# HDMI.net
KiCad netlist of a schematic drawn in Altium Designer
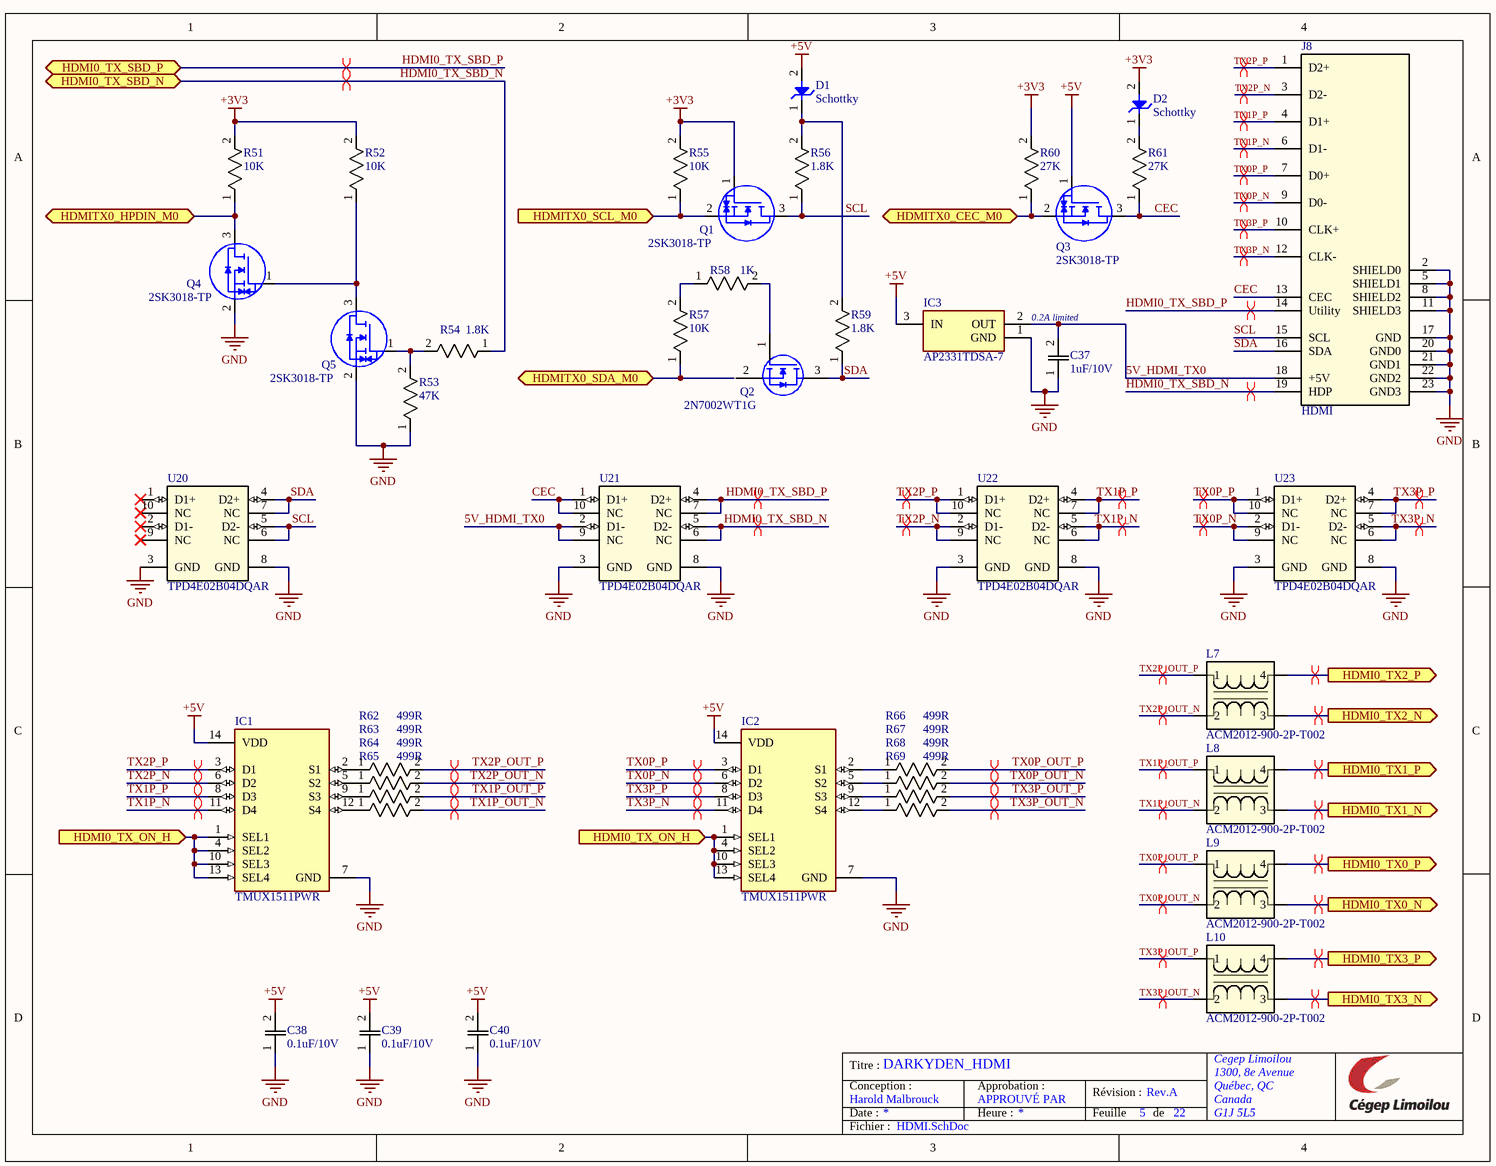
[diagram p0: HDMI.SchDoc]

(export (version "E")
  (design (tool "Eeschema 10.0.6"))
  (components
    (comp (ref "C37")
      (value "1uF/10V")
      (footprint "CAPC220145_100N_KEM")
      (description "Multilayer Ceramic Capacitors MLCC - SMD/SMT 10V 1uF X7R 0805 10%")
      (fields
        (field (name "MANUFACTURER") "KEMET")
        (field (name "MANUFACTURER PART NUMBER") "C0805C105K8RACTU")
      )
      (libsource (lib "C0805C105K8RACTU") (part "C0805C105K8RACTU"))
    )
    (comp (ref "C38")
      (value "0.1uF/10V")
      (footprint "CAPC220145_88N_KEM")
      (description "Cap Ceramic 0.1uF 10V X7R 5% Pad SMD 0805 125C T/R")
      (fields
        (field (name "MANUFACTURER") "KEMET")
        (field (name "MANUFACTURER PART NUMBER") "C0805C104J8RACTU")
      )
      (libsource (lib "C0805C104J8RACTU") (part "C0805C104J8RACTU"))
    )
    (comp (ref "C39")
      (value "0.1uF/10V")
      (footprint "CAPC220145_88N_KEM")
      (description "Cap Ceramic 0.1uF 10V X7R 5% Pad SMD 0805 125C T/R")
      (fields
        (field (name "MANUFACTURER") "KEMET")
        (field (name "MANUFACTURER PART NUMBER") "C0805C104J8RACTU")
      )
      (libsource (lib "C0805C104J8RACTU") (part "C0805C104J8RACTU"))
    )
    (comp (ref "C40")
      (value "0.1uF/10V")
      (footprint "CAPC220145_88N_KEM")
      (description "Cap Ceramic 0.1uF 10V X7R 5% Pad SMD 0805 125C T/R")
      (fields
        (field (name "MANUFACTURER") "KEMET")
        (field (name "MANUFACTURER PART NUMBER") "C0805C104J8RACTU")
      )
      (libsource (lib "C0805C104J8RACTU") (part "C0805C104J8RACTU"))
    )
    (comp (ref "D1")
      (value "Schottky")
      (footprint "SamacSys:SODFL1608X70N")
      (description "Diode -SOD523")
      (fields
        (field (name "MANUFACTURER_PART_NUMBER") "RB520S30T1G")
        (field (name "MOUSER PART NUMBER") "863-RB520S30T1G")
      )
      (libsource (lib "SamacSys") (part "Schottky"))
    )
    (comp (ref "D2")
      (value "Schottky")
      (footprint "SamacSys:SODFL1608X70N")
      (description "Diode -SOD523")
      (fields
        (field (name "MANUFACTURER_PART_NUMBER") "RB520S30T1G")
        (field (name "MOUSER PART NUMBER") "863-RB520S30T1G")
      )
      (libsource (lib "SamacSys") (part "Schottky"))
    )
    (comp (ref "IC1")
      (value "TMUX1511PWR")
      (footprint "SamacSys:SOP65P640X120-14N")
      (fields
        (field (name "MOUSER PART NUMBER") "595-TMUX1511PWR")
        (field (name "MANUFACTURER") "Texas Instruments")
      )
      (libsource (lib "SamacSys") (part "TMUX1511PWR"))
    )
    (comp (ref "IC2")
      (value "TMUX1511PWR")
      (footprint "SamacSys:SOP65P640X120-14N")
      (fields
        (field (name "MOUSER PART NUMBER") "595-TMUX1511PWR")
        (field (name "MANUFACTURER") "Texas Instruments")
      )
      (libsource (lib "SamacSys") (part "TMUX1511PWR"))
    )
    (comp (ref "IC3")
      (value "AP2331TDSA-7")
      (footprint "SamacSys:SOT96P240X110-3N")
      (description "USB Power Switch Single 5.2V 0.4A 3-Pin SOT-23 T/R")
      (fields (field (name "MOUSER PART NUMBER") "621-AP2331TDSA-7") (field (name "MANUFACTURER") "Diodes"))
      (libsource (lib "SamacSys") (part "AP2331TDSA-7"))
    )
    (comp (ref "J8")
      (value "HDMI")
      (footprint "CONN19_2001-1-2-21-00-BK_CNC")
      (description "2001-1-2-21-00-BK")
      (libsource (lib "HDMI") (part "HDMI"))
    )
    (comp (ref "L7")
      (value "ACM2012-900-2P-T002")
      (footprint "SamacSys:ACM20129002PT002")
      (description "Ferrite Beads Wirewound Common Mode Filter 90Ohm 100MHz 400mA 0805 T/R")
      (fields (field (name "MOUSER PART NUMBER") "810-ACM20129002PT002") (field (name "MANUFACTURER") "TDK"))
      (libsource (lib "SamacSys") (part "ACM2012-900-2P-T002"))
    )
    (comp (ref "L8")
      (value "ACM2012-900-2P-T002")
      (footprint "SamacSys:ACM20129002PT002")
      (description "Ferrite Beads Wirewound Common Mode Filter 90Ohm 100MHz 400mA 0805 T/R")
      (fields (field (name "MOUSER PART NUMBER") "810-ACM20129002PT002") (field (name "MANUFACTURER") "TDK"))
      (libsource (lib "SamacSys") (part "ACM2012-900-2P-T002"))
    )
    (comp (ref "L9")
      (value "ACM2012-900-2P-T002")
      (footprint "SamacSys:ACM20129002PT002")
      (description "Ferrite Beads Wirewound Common Mode Filter 90Ohm 100MHz 400mA 0805 T/R")
      (fields (field (name "MOUSER PART NUMBER") "810-ACM20129002PT002") (field (name "MANUFACTURER") "TDK"))
      (libsource (lib "SamacSys") (part "ACM2012-900-2P-T002"))
    )
    (comp (ref "L10")
      (value "ACM2012-900-2P-T002")
      (footprint "SamacSys:ACM20129002PT002")
      (description "Ferrite Beads Wirewound Common Mode Filter 90Ohm 100MHz 400mA 0805 T/R")
      (fields (field (name "MOUSER PART NUMBER") "810-ACM20129002PT002") (field (name "MANUFACTURER") "TDK"))
      (libsource (lib "SamacSys") (part "ACM2012-900-2P-T002"))
    )
    (comp (ref "Q1")
      (value "2SK3018-TP")
      (footprint "SamacSys:SOT65P228X120-3N")
      (description "N-Channel 30 V 100mA (Ta) 200mW (Ta) Surface Mount SOT-323")
      (fields (field (name "MOUSER PART NUMBER") "833-2SK3018-TP"))
      (libsource (lib "SamacSys") (part "2SK3018-TP"))
    )
    (comp (ref "Q2")
      (value "2N7002WT1G")
      (footprint "SOT-323-3_2P2X1P35_ONS")
      (description "No Description Available")
      (libsource (lib "2N7002WT1G") (part "2N7002WT1G"))
    )
    (comp (ref "Q3")
      (value "2SK3018-TP")
      (footprint "SamacSys:SOT65P228X120-3N")
      (description "N-Channel 30 V 100mA (Ta) 200mW (Ta) Surface Mount SOT-323")
      (fields (field (name "MOUSER PART NUMBER") "833-2SK3018-TP"))
      (libsource (lib "SamacSys") (part "2SK3018-TP"))
    )
    (comp (ref "Q4")
      (value "2SK3018-TP")
      (footprint "SamacSys:SOT65P228X120-3N")
      (description "N-Channel 30 V 100mA (Ta) 200mW (Ta) Surface Mount SOT-323")
      (fields (field (name "MOUSER PART NUMBER") "833-2SK3018-TP"))
      (libsource (lib "SamacSys") (part "2SK3018-TP"))
    )
    (comp (ref "Q5")
      (value "2SK3018-TP")
      (footprint "SamacSys:SOT65P228X120-3N")
      (description "N-Channel 30 V 100mA (Ta) 200mW (Ta) Surface Mount SOT-323")
      (fields (field (name "MOUSER PART NUMBER") "833-2SK3018-TP"))
      (libsource (lib "SamacSys") (part "2SK3018-TP"))
    )
    (comp (ref "R51")
      (value "10K")
      (footprint "SamacSys:ERJ3EKF1000V")
      (description "10K Ohm 5% Res Thick Film 0603  0.1W(1/10W) ±200ppm/C Pad SMD Automotive T/R")
      (fields
        (field (name "MANUFACTURER_PART_NUMBER") "ERJ-3GEYJ103V")
        (field (name "MOUSER PART NUMBER") "667-ERJ-3GEYJ103V")
      )
      (libsource (lib "SamacSys") (part "ERJ-3GEYJ103V"))
    )
    (comp (ref "R52")
      (value "10K")
      (footprint "SamacSys:ERJ3EKF1000V")
      (description "10K Ohm 5% Res Thick Film 0603  0.1W(1/10W) ±200ppm/C Pad SMD Automotive T/R")
      (fields
        (field (name "MANUFACTURER_PART_NUMBER") "ERJ-3GEYJ103V")
        (field (name "MOUSER PART NUMBER") "667-ERJ-3GEYJ103V")
      )
      (libsource (lib "SamacSys") (part "ERJ-3GEYJ103V"))
    )
    (comp (ref "R53")
      (value "47K")
      (footprint "RC0603N_PAN")
      (description "Resistor Thick Film 0603 47K Ohm 5% 1/10W 200ppm/C Molded SMD Punched Carrier T/R")
      (fields
        (field (name "MANUFACTURER") "Panasonic")
        (field (name "MANUFACTURER PART NUMBER") "ERJ-3GEYJ473V")
      )
      (libsource (lib "ERJ-3GEYJ473V") (part "ERJ-3GEYJ473V"))
    )
    (comp (ref "R54")
      (value "1.8K")
      (footprint "RC0603N_PAN")
      (description "SMD Chip Resistor, 1.8 kOhm, ± 5%, 100 mW, 0603 [1608 Metric], Thick Film, General Purpose")
      (fields
        (field (name "MANUFACTURER") "Panasonic")
        (field (name "MANUFACTURER PART NUMBER") "ERJ-3GEYJ182V")
      )
      (libsource (lib "ERJ-3GEYJ182V") (part "ERJ-3GEYJ182V"))
    )
    (comp (ref "R55")
      (value "10K")
      (footprint "SamacSys:ERJ3EKF1000V")
      (description "10K Ohm 5% Res Thick Film 0603  0.1W(1/10W) ±200ppm/C Pad SMD Automotive T/R")
      (fields
        (field (name "MANUFACTURER_PART_NUMBER") "ERJ-3GEYJ103V")
        (field (name "MOUSER PART NUMBER") "667-ERJ-3GEYJ103V")
      )
      (libsource (lib "SamacSys") (part "ERJ-3GEYJ103V"))
    )
    (comp (ref "R56")
      (value "1.8K")
      (footprint "RC0603N_PAN")
      (description "SMD Chip Resistor, 1.8 kOhm, ± 5%, 100 mW, 0603 [1608 Metric], Thick Film, General Purpose")
      (fields
        (field (name "MANUFACTURER") "Panasonic")
        (field (name "MANUFACTURER PART NUMBER") "ERJ-3GEYJ182V")
      )
      (libsource (lib "ERJ-3GEYJ182V") (part "ERJ-3GEYJ182V"))
    )
    (comp (ref "R57")
      (value "10K")
      (footprint "SamacSys:ERJ3EKF1000V")
      (description "10K Ohm 5% Res Thick Film 0603  0.1W(1/10W) ±200ppm/C Pad SMD Automotive T/R")
      (fields
        (field (name "MANUFACTURER_PART_NUMBER") "ERJ-3GEYJ103V")
        (field (name "MOUSER PART NUMBER") "667-ERJ-3GEYJ103V")
      )
      (libsource (lib "SamacSys") (part "ERJ-3GEYJ103V"))
    )
    (comp (ref "R58")
      (value "1K")
      (footprint "SamacSys:RESC1608X55N")
      (description "1K Ohm 1% 1/10W Res Thick Film 0603 ±100ppm/°C Molded SMD Punched Carrier T/R")
      (fields
        (field (name "MANUFACTURER_PART_NUMBER") "ERJ-3EKF1001V")
        (field (name "MOUSER PART NUMBER") "667-ERJ-3EKF1001V")
      )
      (libsource (lib "SamacSys") (part "ERJ-3EKF1001V"))
    )
    (comp (ref "R59")
      (value "1.8K")
      (footprint "RC0603N_PAN")
      (description "SMD Chip Resistor, 1.8 kOhm, ± 5%, 100 mW, 0603 [1608 Metric], Thick Film, General Purpose")
      (fields
        (field (name "MANUFACTURER") "Panasonic")
        (field (name "MANUFACTURER PART NUMBER") "ERJ-3GEYJ182V")
      )
      (libsource (lib "ERJ-3GEYJ182V") (part "ERJ-3GEYJ182V"))
    )
    (comp (ref "R60")
      (value "27K")
      (footprint "RC0603N_PAN")
      (description "Res Thick Film 0603 27K Ohm 1% 1/10W ±100ppm/°C Molded SMD Punched Carrier T/R")
      (fields
        (field (name "MANUFACTURER") "Panasonic")
        (field (name "MANUFACTURER PART NUMBER") "ERJ-3EKF2702V")
      )
      (libsource (lib "ERJ-3EKF2702V") (part "ERJ-3EKF2702V"))
    )
    (comp (ref "R61")
      (value "27K")
      (footprint "RC0603N_PAN")
      (description "Res Thick Film 0603 27K Ohm 1% 1/10W ±100ppm/°C Molded SMD Punched Carrier T/R")
      (fields
        (field (name "MANUFACTURER") "Panasonic")
        (field (name "MANUFACTURER PART NUMBER") "ERJ-3EKF2702V")
      )
      (libsource (lib "ERJ-3EKF2702V") (part "ERJ-3EKF2702V"))
    )
    (comp (ref "R62")
      (value "499R")
      (footprint "RC0603N_PAN")
      (description "SMD Chip Resistor, 499 Ohm, ï¿½ 1%, 100 mW, 0603 [1608 Metric], Thick Film, Precision")
      (fields
        (field (name "MANUFACTURER") "Panasonic")
        (field (name "MANUFACTURER PART NUMBER") "ERJ-3EKF4990V")
      )
      (libsource (lib "ERJ-3EKF4990V") (part "ERJ-3EKF4990V"))
    )
    (comp (ref "R63")
      (value "499R")
      (footprint "RC0603N_PAN")
      (description "SMD Chip Resistor, 499 Ohm, ï¿½ 1%, 100 mW, 0603 [1608 Metric], Thick Film, Precision")
      (fields
        (field (name "MANUFACTURER") "Panasonic")
        (field (name "MANUFACTURER PART NUMBER") "ERJ-3EKF4990V")
      )
      (libsource (lib "ERJ-3EKF4990V") (part "ERJ-3EKF4990V"))
    )
    (comp (ref "R64")
      (value "499R")
      (footprint "RC0603N_PAN")
      (description "SMD Chip Resistor, 499 Ohm, ï¿½ 1%, 100 mW, 0603 [1608 Metric], Thick Film, Precision")
      (fields
        (field (name "MANUFACTURER") "Panasonic")
        (field (name "MANUFACTURER PART NUMBER") "ERJ-3EKF4990V")
      )
      (libsource (lib "ERJ-3EKF4990V") (part "ERJ-3EKF4990V"))
    )
    (comp (ref "R65")
      (value "499R")
      (footprint "RC0603N_PAN")
      (description "SMD Chip Resistor, 499 Ohm, ï¿½ 1%, 100 mW, 0603 [1608 Metric], Thick Film, Precision")
      (fields
        (field (name "MANUFACTURER") "Panasonic")
        (field (name "MANUFACTURER PART NUMBER") "ERJ-3EKF4990V")
      )
      (libsource (lib "ERJ-3EKF4990V") (part "ERJ-3EKF4990V"))
    )
    (comp (ref "R66")
      (value "499R")
      (footprint "RC0603N_PAN")
      (description "SMD Chip Resistor, 499 Ohm, ï¿½ 1%, 100 mW, 0603 [1608 Metric], Thick Film, Precision")
      (fields
        (field (name "MANUFACTURER") "Panasonic")
        (field (name "MANUFACTURER PART NUMBER") "ERJ-3EKF4990V")
      )
      (libsource (lib "ERJ-3EKF4990V") (part "ERJ-3EKF4990V"))
    )
    (comp (ref "R67")
      (value "499R")
      (footprint "RC0603N_PAN")
      (description "SMD Chip Resistor, 499 Ohm, ï¿½ 1%, 100 mW, 0603 [1608 Metric], Thick Film, Precision")
      (fields
        (field (name "MANUFACTURER") "Panasonic")
        (field (name "MANUFACTURER PART NUMBER") "ERJ-3EKF4990V")
      )
      (libsource (lib "ERJ-3EKF4990V") (part "ERJ-3EKF4990V"))
    )
    (comp (ref "R68")
      (value "499R")
      (footprint "RC0603N_PAN")
      (description "SMD Chip Resistor, 499 Ohm, ï¿½ 1%, 100 mW, 0603 [1608 Metric], Thick Film, Precision")
      (fields
        (field (name "MANUFACTURER") "Panasonic")
        (field (name "MANUFACTURER PART NUMBER") "ERJ-3EKF4990V")
      )
      (libsource (lib "ERJ-3EKF4990V") (part "ERJ-3EKF4990V"))
    )
    (comp (ref "R69")
      (value "499R")
      (footprint "RC0603N_PAN")
      (description "SMD Chip Resistor, 499 Ohm, ï¿½ 1%, 100 mW, 0603 [1608 Metric], Thick Film, Precision")
      (fields
        (field (name "MANUFACTURER") "Panasonic")
        (field (name "MANUFACTURER PART NUMBER") "ERJ-3EKF4990V")
      )
      (libsource (lib "ERJ-3EKF4990V") (part "ERJ-3EKF4990V"))
    )
    (comp (ref "U20")
      (value "TPD4E02B04DQAR")
      (footprint "DQA0010A")
      (description "TVS DIODE 3.6V 8.8V 10USON / 4-Channel ESD Protection Diode for USB Type-C and HDMI 2.0")
      (fields (field (name "MANUFACTURER") "Texas Instruments"))
      (libsource (lib "TPD4E02B04DQAR") (part "TPD4E02B04DQAR"))
    )
    (comp (ref "U21")
      (value "TPD4E02B04DQAR")
      (footprint "DQA0010A")
      (description "TVS DIODE 3.6V 8.8V 10USON / 4-Channel ESD Protection Diode for USB Type-C and HDMI 2.0")
      (fields (field (name "MANUFACTURER") "Texas Instruments"))
      (libsource (lib "TPD4E02B04DQAR") (part "TPD4E02B04DQAR"))
    )
    (comp (ref "U22")
      (value "TPD4E02B04DQAR")
      (footprint "DQA0010A")
      (description "TVS DIODE 3.6V 8.8V 10USON / 4-Channel ESD Protection Diode for USB Type-C and HDMI 2.0")
      (fields (field (name "MANUFACTURER") "Texas Instruments"))
      (libsource (lib "TPD4E02B04DQAR") (part "TPD4E02B04DQAR"))
    )
    (comp (ref "U23")
      (value "TPD4E02B04DQAR")
      (footprint "DQA0010A")
      (description "TVS DIODE 3.6V 8.8V 10USON / 4-Channel ESD Protection Diode for USB Type-C and HDMI 2.0")
      (fields (field (name "MANUFACTURER") "Texas Instruments"))
      (libsource (lib "TPD4E02B04DQAR") (part "TPD4E02B04DQAR"))
    )
  )
  (nets
    (net (code "1") (name "+3V3") (class "Default")
      (node (ref "D2") (pin "2") (pinfunction "A_2") (pintype "passive"))
      (node (ref "Q1") (pin "1") (pinfunction "G_1") (pintype "passive"))
      (node (ref "R51") (pin "2") (pinfunction "2_2") (pintype "passive"))
      (node (ref "R52") (pin "2") (pinfunction "2_2") (pintype "passive"))
      (node (ref "R55") (pin "2") (pinfunction "2_2") (pintype "passive"))
      (node (ref "R60") (pin "2") (pinfunction "2_2") (pintype "passive"))
    )
    (net (code "2") (name "+5V") (class "Default")
      (node (ref "C38") (pin "2") (pinfunction "2_2") (pintype "passive"))
      (node (ref "C39") (pin "2") (pinfunction "2_2") (pintype "passive"))
      (node (ref "C40") (pin "2") (pinfunction "2_2") (pintype "passive"))
      (node (ref "D1") (pin "2") (pinfunction "A_2") (pintype "passive"))
      (node (ref "IC1") (pin "14") (pinfunction "VDD_14") (pintype "power_in"))
      (node (ref "IC2") (pin "14") (pinfunction "VDD_14") (pintype "power_in"))
      (node (ref "IC3") (pin "3") (pinfunction "IN_3") (pintype "passive"))
      (node (ref "Q3") (pin "1") (pinfunction "G_1") (pintype "passive"))
    )
    (net (code "3") (name "/5V_HDMI_TX0") (class "Default")
      (node (ref "C37") (pin "2") (pinfunction "2_2") (pintype "passive"))
      (node (ref "IC3") (pin "2") (pinfunction "OUT_2") (pintype "passive"))
      (node (ref "J8") (pin "18") (pinfunction "+5V_18") (pintype "passive"))
      (node (ref "U21") (pin "2") (pinfunction "D1-_2") (pintype "bidirectional"))
      (node (ref "U21") (pin "9") (pinfunction "NC_9") (pintype "passive"))
    )
    (net (code "4") (name "/CEC") (class "Default")
      (node (ref "J8") (pin "13") (pinfunction "CEC_13") (pintype "passive"))
      (node (ref "Q3") (pin "3") (pinfunction "D_3") (pintype "passive"))
      (node (ref "R61") (pin "1") (pinfunction "1_1") (pintype "passive"))
      (node (ref "U21") (pin "1") (pinfunction "D1+_1") (pintype "bidirectional"))
      (node (ref "U21") (pin "10") (pinfunction "NC_10") (pintype "passive"))
    )
    (net (code "5") (name "/HDMI0_TX0_N") (class "Default")
      (node (ref "L9") (pin "3") (pinfunction "3_3") (pintype "passive"))
    )
    (net (code "6") (name "/HDMI0_TX0_P") (class "Default")
      (node (ref "L9") (pin "4") (pinfunction "4_4") (pintype "passive"))
    )
    (net (code "7") (name "/HDMI0_TX1_N") (class "Default")
      (node (ref "L8") (pin "3") (pinfunction "3_3") (pintype "passive"))
    )
    (net (code "8") (name "/HDMI0_TX1_P") (class "Default")
      (node (ref "L8") (pin "4") (pinfunction "4_4") (pintype "passive"))
    )
    (net (code "9") (name "/HDMI0_TX2_N") (class "Default")
      (node (ref "L7") (pin "3") (pinfunction "3_3") (pintype "passive"))
    )
    (net (code "10") (name "/HDMI0_TX2_P") (class "Default")
      (node (ref "L7") (pin "4") (pinfunction "4_4") (pintype "passive"))
    )
    (net (code "11") (name "/HDMI0_TX3_N") (class "Default")
      (node (ref "L10") (pin "3") (pinfunction "3_3") (pintype "passive"))
    )
    (net (code "12") (name "/HDMI0_TX3_P") (class "Default")
      (node (ref "L10") (pin "4") (pinfunction "4_4") (pintype "passive"))
    )
    (net (code "13") (name "/HDMI0_TX_ON_H") (class "Default")
      (node (ref "IC1") (pin "1") (pinfunction "SEL1_1") (pintype "input"))
      (node (ref "IC1") (pin "10") (pinfunction "SEL3_10") (pintype "input"))
      (node (ref "IC1") (pin "13") (pinfunction "SEL4_13") (pintype "input"))
      (node (ref "IC1") (pin "4") (pinfunction "SEL2_4") (pintype "input"))
      (node (ref "IC2") (pin "1") (pinfunction "SEL1_1") (pintype "input"))
      (node (ref "IC2") (pin "10") (pinfunction "SEL3_10") (pintype "input"))
      (node (ref "IC2") (pin "13") (pinfunction "SEL4_13") (pintype "input"))
      (node (ref "IC2") (pin "4") (pinfunction "SEL2_4") (pintype "input"))
    )
    (net (code "14") (name "/HDMI0_TX_SBD_N") (class "Default")
      (node (ref "J8") (pin "19") (pinfunction "HDP_19") (pintype "passive"))
      (node (ref "R54") (pin "1") (pinfunction "1_1") (pintype "passive"))
      (node (ref "U21") (pin "5") (pinfunction "D2-_5") (pintype "bidirectional"))
      (node (ref "U21") (pin "6") (pinfunction "NC_6") (pintype "passive"))
    )
    (net (code "15") (name "/HDMI0_TX_SBD_P") (class "Default")
      (node (ref "J8") (pin "14") (pinfunction "Utility_14") (pintype "passive"))
      (node (ref "U21") (pin "4") (pinfunction "D2+_4") (pintype "bidirectional"))
      (node (ref "U21") (pin "7") (pinfunction "NC_7") (pintype "passive"))
    )
    (net (code "16") (name "/HDMITX0_CEC_M0") (class "Default")
      (node (ref "Q3") (pin "2") (pinfunction "S_2") (pintype "passive"))
      (node (ref "R60") (pin "1") (pinfunction "1_1") (pintype "passive"))
    )
    (net (code "17") (name "/HDMITX0_HPDIN_M0") (class "Default")
      (node (ref "Q4") (pin "3") (pinfunction "D_3") (pintype "passive"))
      (node (ref "R51") (pin "1") (pinfunction "1_1") (pintype "passive"))
    )
    (net (code "18") (name "/HDMITX0_SCL_M0") (class "Default")
      (node (ref "Q1") (pin "2") (pinfunction "S_2") (pintype "passive"))
      (node (ref "R55") (pin "1") (pinfunction "1_1") (pintype "passive"))
    )
    (net (code "19") (name "/HDMITX0_SDA_M0") (class "Default")
      (node (ref "R57") (pin "1") (pinfunction "1_1") (pintype "passive"))
    )
    (net (code "20") (name "/SCL") (class "Default")
      (node (ref "J8") (pin "15") (pinfunction "SCL_15") (pintype "passive"))
      (node (ref "Q1") (pin "3") (pinfunction "D_3") (pintype "passive"))
      (node (ref "R56") (pin "1") (pinfunction "1_1") (pintype "passive"))
      (node (ref "U20") (pin "5") (pinfunction "D2-_5") (pintype "bidirectional"))
      (node (ref "U20") (pin "6") (pinfunction "NC_6") (pintype "passive"))
    )
    (net (code "21") (name "/SDA") (class "Default")
      (node (ref "J8") (pin "16") (pinfunction "SDA_16") (pintype "passive"))
      (node (ref "Q2") (pin "3") (pinfunction "DRAIN_3") (pintype "passive"))
      (node (ref "R59") (pin "1") (pinfunction "1_1") (pintype "passive"))
      (node (ref "U20") (pin "4") (pinfunction "D2+_4") (pintype "bidirectional"))
      (node (ref "U20") (pin "7") (pinfunction "NC_7") (pintype "passive"))
    )
    (net (code "22") (name "/TX0P_N") (class "Default")
      (node (ref "IC2") (pin "6") (pinfunction "D2_6") (pintype "bidirectional"))
      (node (ref "J8") (pin "9") (pinfunction "D0-_9") (pintype "passive"))
      (node (ref "U23") (pin "2") (pinfunction "D1-_2") (pintype "bidirectional"))
      (node (ref "U23") (pin "9") (pinfunction "NC_9") (pintype "passive"))
    )
    (net (code "23") (name "/TX0P_OUT_N") (class "Default")
      (node (ref "L9") (pin "2") (pinfunction "2_2") (pintype "passive"))
      (node (ref "R67") (pin "2") (pinfunction "2_2") (pintype "passive"))
    )
    (net (code "24") (name "/TX0P_OUT_P") (class "Default")
      (node (ref "L9") (pin "1") (pinfunction "1_1") (pintype "passive"))
      (node (ref "R66") (pin "2") (pinfunction "2_2") (pintype "passive"))
    )
    (net (code "25") (name "/TX0P_P") (class "Default")
      (node (ref "IC2") (pin "3") (pinfunction "D1_3") (pintype "bidirectional"))
      (node (ref "J8") (pin "7") (pinfunction "D0+_7") (pintype "passive"))
      (node (ref "U23") (pin "1") (pinfunction "D1+_1") (pintype "bidirectional"))
      (node (ref "U23") (pin "10") (pinfunction "NC_10") (pintype "passive"))
    )
    (net (code "26") (name "/TX1P_N") (class "Default")
      (node (ref "IC1") (pin "11") (pinfunction "D4_11") (pintype "bidirectional"))
      (node (ref "J8") (pin "6") (pinfunction "D1-_6") (pintype "passive"))
      (node (ref "U22") (pin "5") (pinfunction "D2-_5") (pintype "bidirectional"))
      (node (ref "U22") (pin "6") (pinfunction "NC_6") (pintype "passive"))
    )
    (net (code "27") (name "/TX1P_OUT_N") (class "Default")
      (node (ref "L8") (pin "2") (pinfunction "2_2") (pintype "passive"))
      (node (ref "R65") (pin "2") (pinfunction "2_2") (pintype "passive"))
    )
    (net (code "28") (name "/TX1P_OUT_P") (class "Default")
      (node (ref "L8") (pin "1") (pinfunction "1_1") (pintype "passive"))
      (node (ref "R64") (pin "2") (pinfunction "2_2") (pintype "passive"))
    )
    (net (code "29") (name "/TX1P_P") (class "Default")
      (node (ref "IC1") (pin "8") (pinfunction "D3_8") (pintype "bidirectional"))
      (node (ref "J8") (pin "4") (pinfunction "D1+_4") (pintype "passive"))
      (node (ref "U22") (pin "4") (pinfunction "D2+_4") (pintype "bidirectional"))
      (node (ref "U22") (pin "7") (pinfunction "NC_7") (pintype "passive"))
    )
    (net (code "30") (name "/TX2P_N") (class "Default")
      (node (ref "IC1") (pin "6") (pinfunction "D2_6") (pintype "bidirectional"))
      (node (ref "J8") (pin "3") (pinfunction "D2-_3") (pintype "passive"))
      (node (ref "U22") (pin "2") (pinfunction "D1-_2") (pintype "bidirectional"))
      (node (ref "U22") (pin "9") (pinfunction "NC_9") (pintype "passive"))
    )
    (net (code "31") (name "/TX2P_OUT_N") (class "Default")
      (node (ref "L7") (pin "2") (pinfunction "2_2") (pintype "passive"))
      (node (ref "R63") (pin "2") (pinfunction "2_2") (pintype "passive"))
    )
    (net (code "32") (name "/TX2P_OUT_P") (class "Default")
      (node (ref "L7") (pin "1") (pinfunction "1_1") (pintype "passive"))
      (node (ref "R62") (pin "2") (pinfunction "2_2") (pintype "passive"))
    )
    (net (code "33") (name "/TX2P_P") (class "Default")
      (node (ref "IC1") (pin "3") (pinfunction "D1_3") (pintype "bidirectional"))
      (node (ref "J8") (pin "1") (pinfunction "D2+_1") (pintype "passive"))
      (node (ref "U22") (pin "1") (pinfunction "D1+_1") (pintype "bidirectional"))
      (node (ref "U22") (pin "10") (pinfunction "NC_10") (pintype "passive"))
    )
    (net (code "34") (name "/TX3P_N") (class "Default")
      (node (ref "IC2") (pin "11") (pinfunction "D4_11") (pintype "bidirectional"))
      (node (ref "J8") (pin "12") (pinfunction "CLK-_12") (pintype "passive"))
      (node (ref "U23") (pin "5") (pinfunction "D2-_5") (pintype "bidirectional"))
      (node (ref "U23") (pin "6") (pinfunction "NC_6") (pintype "passive"))
    )
    (net (code "35") (name "/TX3P_OUT_N") (class "Default")
      (node (ref "L10") (pin "2") (pinfunction "2_2") (pintype "passive"))
      (node (ref "R69") (pin "2") (pinfunction "2_2") (pintype "passive"))
    )
    (net (code "36") (name "/TX3P_OUT_P") (class "Default")
      (node (ref "L10") (pin "1") (pinfunction "1_1") (pintype "passive"))
      (node (ref "R68") (pin "2") (pinfunction "2_2") (pintype "passive"))
    )
    (net (code "37") (name "/TX3P_P") (class "Default")
      (node (ref "IC2") (pin "8") (pinfunction "D3_8") (pintype "bidirectional"))
      (node (ref "J8") (pin "10") (pinfunction "CLK+_10") (pintype "passive"))
      (node (ref "U23") (pin "4") (pinfunction "D2+_4") (pintype "bidirectional"))
      (node (ref "U23") (pin "7") (pinfunction "NC_7") (pintype "passive"))
    )
    (net (code "38") (name "GND") (class "Default")
      (node (ref "C37") (pin "1") (pinfunction "1_1") (pintype "passive"))
      (node (ref "C38") (pin "1") (pinfunction "1_1") (pintype "passive"))
      (node (ref "C39") (pin "1") (pinfunction "1_1") (pintype "passive"))
      (node (ref "C40") (pin "1") (pinfunction "1_1") (pintype "passive"))
      (node (ref "IC1") (pin "7") (pinfunction "GND_7") (pintype "power_in"))
      (node (ref "IC2") (pin "7") (pinfunction "GND_7") (pintype "power_in"))
      (node (ref "IC3") (pin "1") (pinfunction "GND_1") (pintype "passive"))
      (node (ref "J8") (pin "11") (pinfunction "SHIELD3_11") (pintype "passive"))
      (node (ref "J8") (pin "17") (pinfunction "GND_17") (pintype "passive"))
      (node (ref "J8") (pin "2") (pinfunction "SHIELD0_2") (pintype "passive"))
      (node (ref "J8") (pin "20") (pinfunction "GND0_20") (pintype "passive"))
      (node (ref "J8") (pin "21") (pinfunction "GND1_21") (pintype "passive"))
      (node (ref "J8") (pin "22") (pinfunction "GND2_22") (pintype "passive"))
      (node (ref "J8") (pin "23") (pinfunction "GND3_23") (pintype "passive"))
      (node (ref "J8") (pin "5") (pinfunction "SHIELD1_5") (pintype "passive"))
      (node (ref "J8") (pin "8") (pinfunction "SHIELD2_8") (pintype "passive"))
      (node (ref "Q4") (pin "2") (pinfunction "S_2") (pintype "passive"))
      (node (ref "Q5") (pin "2") (pinfunction "S_2") (pintype "passive"))
      (node (ref "R53") (pin "1") (pinfunction "1_1") (pintype "passive"))
      (node (ref "U20") (pin "3") (pinfunction "GND_3") (pintype "passive"))
      (node (ref "U20") (pin "8") (pinfunction "GND_8") (pintype "passive"))
      (node (ref "U21") (pin "3") (pinfunction "GND_3") (pintype "passive"))
      (node (ref "U21") (pin "8") (pinfunction "GND_8") (pintype "passive"))
      (node (ref "U22") (pin "3") (pinfunction "GND_3") (pintype "passive"))
      (node (ref "U22") (pin "8") (pinfunction "GND_8") (pintype "passive"))
      (node (ref "U23") (pin "3") (pinfunction "GND_3") (pintype "passive"))
      (node (ref "U23") (pin "8") (pinfunction "GND_8") (pintype "passive"))
    )
    (net (code "39") (name "Net-(D1-K)") (class "Default")
      (node (ref "D1") (pin "1") (pinfunction "K_1") (pintype "passive"))
      (node (ref "R56") (pin "2") (pinfunction "2_2") (pintype "passive"))
      (node (ref "R59") (pin "2") (pinfunction "2_2") (pintype "passive"))
    )
    (net (code "40") (name "Net-(D2-K)") (class "Default")
      (node (ref "D2") (pin "1") (pinfunction "K_1") (pintype "passive"))
      (node (ref "R61") (pin "2") (pinfunction "2_2") (pintype "passive"))
    )
    (net (code "41") (name "Net-(IC1-S1)") (class "Default")
      (node (ref "IC1") (pin "2") (pinfunction "S1_2") (pintype "bidirectional"))
      (node (ref "R62") (pin "1") (pinfunction "1_1") (pintype "passive"))
    )
    (net (code "42") (name "Net-(IC1-S2)") (class "Default")
      (node (ref "IC1") (pin "5") (pinfunction "S2_5") (pintype "bidirectional"))
      (node (ref "R63") (pin "1") (pinfunction "1_1") (pintype "passive"))
    )
    (net (code "43") (name "Net-(IC1-S3)") (class "Default")
      (node (ref "IC1") (pin "9") (pinfunction "S3_9") (pintype "bidirectional"))
      (node (ref "R64") (pin "1") (pinfunction "1_1") (pintype "passive"))
    )
    (net (code "44") (name "Net-(IC1-S4)") (class "Default")
      (node (ref "IC1") (pin "12") (pinfunction "S4_12") (pintype "bidirectional"))
      (node (ref "R65") (pin "1") (pinfunction "1_1") (pintype "passive"))
    )
    (net (code "45") (name "Net-(IC2-S1)") (class "Default")
      (node (ref "IC2") (pin "2") (pinfunction "S1_2") (pintype "bidirectional"))
      (node (ref "R66") (pin "1") (pinfunction "1_1") (pintype "passive"))
    )
    (net (code "46") (name "Net-(IC2-S2)") (class "Default")
      (node (ref "IC2") (pin "5") (pinfunction "S2_5") (pintype "bidirectional"))
      (node (ref "R67") (pin "1") (pinfunction "1_1") (pintype "passive"))
    )
    (net (code "47") (name "Net-(IC2-S3)") (class "Default")
      (node (ref "IC2") (pin "9") (pinfunction "S3_9") (pintype "bidirectional"))
      (node (ref "R68") (pin "1") (pinfunction "1_1") (pintype "passive"))
    )
    (net (code "48") (name "Net-(IC2-S4)") (class "Default")
      (node (ref "IC2") (pin "12") (pinfunction "S4_12") (pintype "bidirectional"))
      (node (ref "R69") (pin "1") (pinfunction "1_1") (pintype "passive"))
    )
    (net (code "49") (name "Net-(Q2-GATE)") (class "Default")
      (node (ref "Q2") (pin "1") (pinfunction "GATE_1") (pintype "passive"))
      (node (ref "R58") (pin "2") (pinfunction "2_2") (pintype "passive"))
    )
    (net (code "50") (name "Net-(Q4-G)") (class "Default")
      (node (ref "Q4") (pin "1") (pinfunction "G_1") (pintype "passive"))
      (node (ref "Q5") (pin "3") (pinfunction "D_3") (pintype "passive"))
      (node (ref "R52") (pin "1") (pinfunction "1_1") (pintype "passive"))
    )
    (net (code "51") (name "Net-(Q5-G)") (class "Default")
      (node (ref "Q5") (pin "1") (pinfunction "G_1") (pintype "passive"))
      (node (ref "R53") (pin "2") (pinfunction "2_2") (pintype "passive"))
      (node (ref "R54") (pin "2") (pinfunction "2_2") (pintype "passive"))
    )
    (net (code "52") (name "Net-(R57-Pad2)") (class "Default")
      (node (ref "R57") (pin "2") (pinfunction "2_2") (pintype "passive"))
      (node (ref "R58") (pin "1") (pinfunction "1_1") (pintype "passive"))
    )
    (net (code "53") (name "unconnected-(Q2-SOURCE-Pad2)") (class "Default")
      (node (ref "Q2") (pin "2") (pinfunction "SOURCE_2") (pintype "passive"))
    )
    (net (code "54") (name "unconnected-(U20-D1+-Pad1)") (class "Default")
      (node (ref "U20") (pin "1") (pinfunction "D1+_1") (pintype "bidirectional+no_connect"))
    )
    (net (code "55") (name "unconnected-(U20-D1--Pad2)") (class "Default")
      (node (ref "U20") (pin "2") (pinfunction "D1-_2") (pintype "bidirectional+no_connect"))
    )
    (net (code "56") (name "unconnected-(U20-NC-Pad9)") (class "Default")
      (node (ref "U20") (pin "9") (pinfunction "NC_9") (pintype "passive+no_connect"))
    )
    (net (code "57") (name "unconnected-(U20-NC-Pad10)") (class "Default")
      (node (ref "U20") (pin "10") (pinfunction "NC_10") (pintype "passive+no_connect"))
    )
  )
)
